# eeprom24c32.net
KiCad netlist of a schematic drawn in Altium Designer
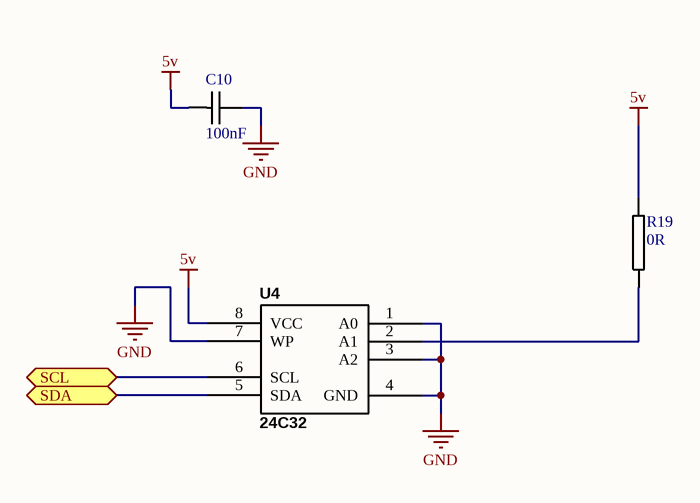
[diagram p0: eeprom24c32.SchDoc]

(export (version "E")
  (design (tool "Eeschema 10.0.6"))
  (components
    (comp (ref "C10")
      (value "100nF")
      (footprint "0805C-TBD")
      (description "CAPACITOR 0805 CERAMIC")
      (libsource (lib "vh_altium_library") (part "0805C-100nF-25V-X7R-MUR"))
    )
    (comp (ref "R19")
      (value "0R")
      (footprint "0805R-GENERIC")
      (description "RESISTOR 0805 1 WATT")
      (libsource (lib "vh_altium_library") (part "0805R-0R"))
    )
    (comp (ref "U4")
      (value "24C32")
      (footprint "SO8")
      (description "IC EEPROM 32KBIT 400KHZ 8SOIC")
      (fields (field (name "MANUFACTURER PART NUMBER") "M24C32-WMN6TP"))
      (libsource (lib "vh_altium_library") (part "24C32"))
    )
  )
  (nets
    (net (code "1") (name "/SCL") (class "Default")
      (node (ref "U4") (pin "6") (pinfunction "SCL_6") (pintype "passive"))
    )
    (net (code "2") (name "/SDA") (class "Default")
      (node (ref "U4") (pin "5") (pinfunction "SDA_5") (pintype "passive"))
    )
    (net (code "3") (name "5v") (class "Default")
      (node (ref "C10") (pin "1") (pintype "passive"))
      (node (ref "R19") (pin "2") (pintype "passive"))
      (node (ref "U4") (pin "8") (pinfunction "VCC_8") (pintype "passive"))
    )
    (net (code "4") (name "GND") (class "Default")
      (node (ref "C10") (pin "2") (pintype "passive"))
      (node (ref "U4") (pin "1") (pinfunction "A0_1") (pintype "passive"))
      (node (ref "U4") (pin "3") (pinfunction "A2_3") (pintype "passive"))
      (node (ref "U4") (pin "4") (pinfunction "GND_4") (pintype "passive"))
      (node (ref "U4") (pin "7") (pinfunction "WP_7") (pintype "passive"))
    )
    (net (code "5") (name "Net-(U4-A1)") (class "Default")
      (node (ref "R19") (pin "1") (pintype "passive"))
      (node (ref "U4") (pin "2") (pinfunction "A1_2") (pintype "passive"))
    )
  )
)
